# test.net
KiCad netlist of a schematic drawn in EAGLE
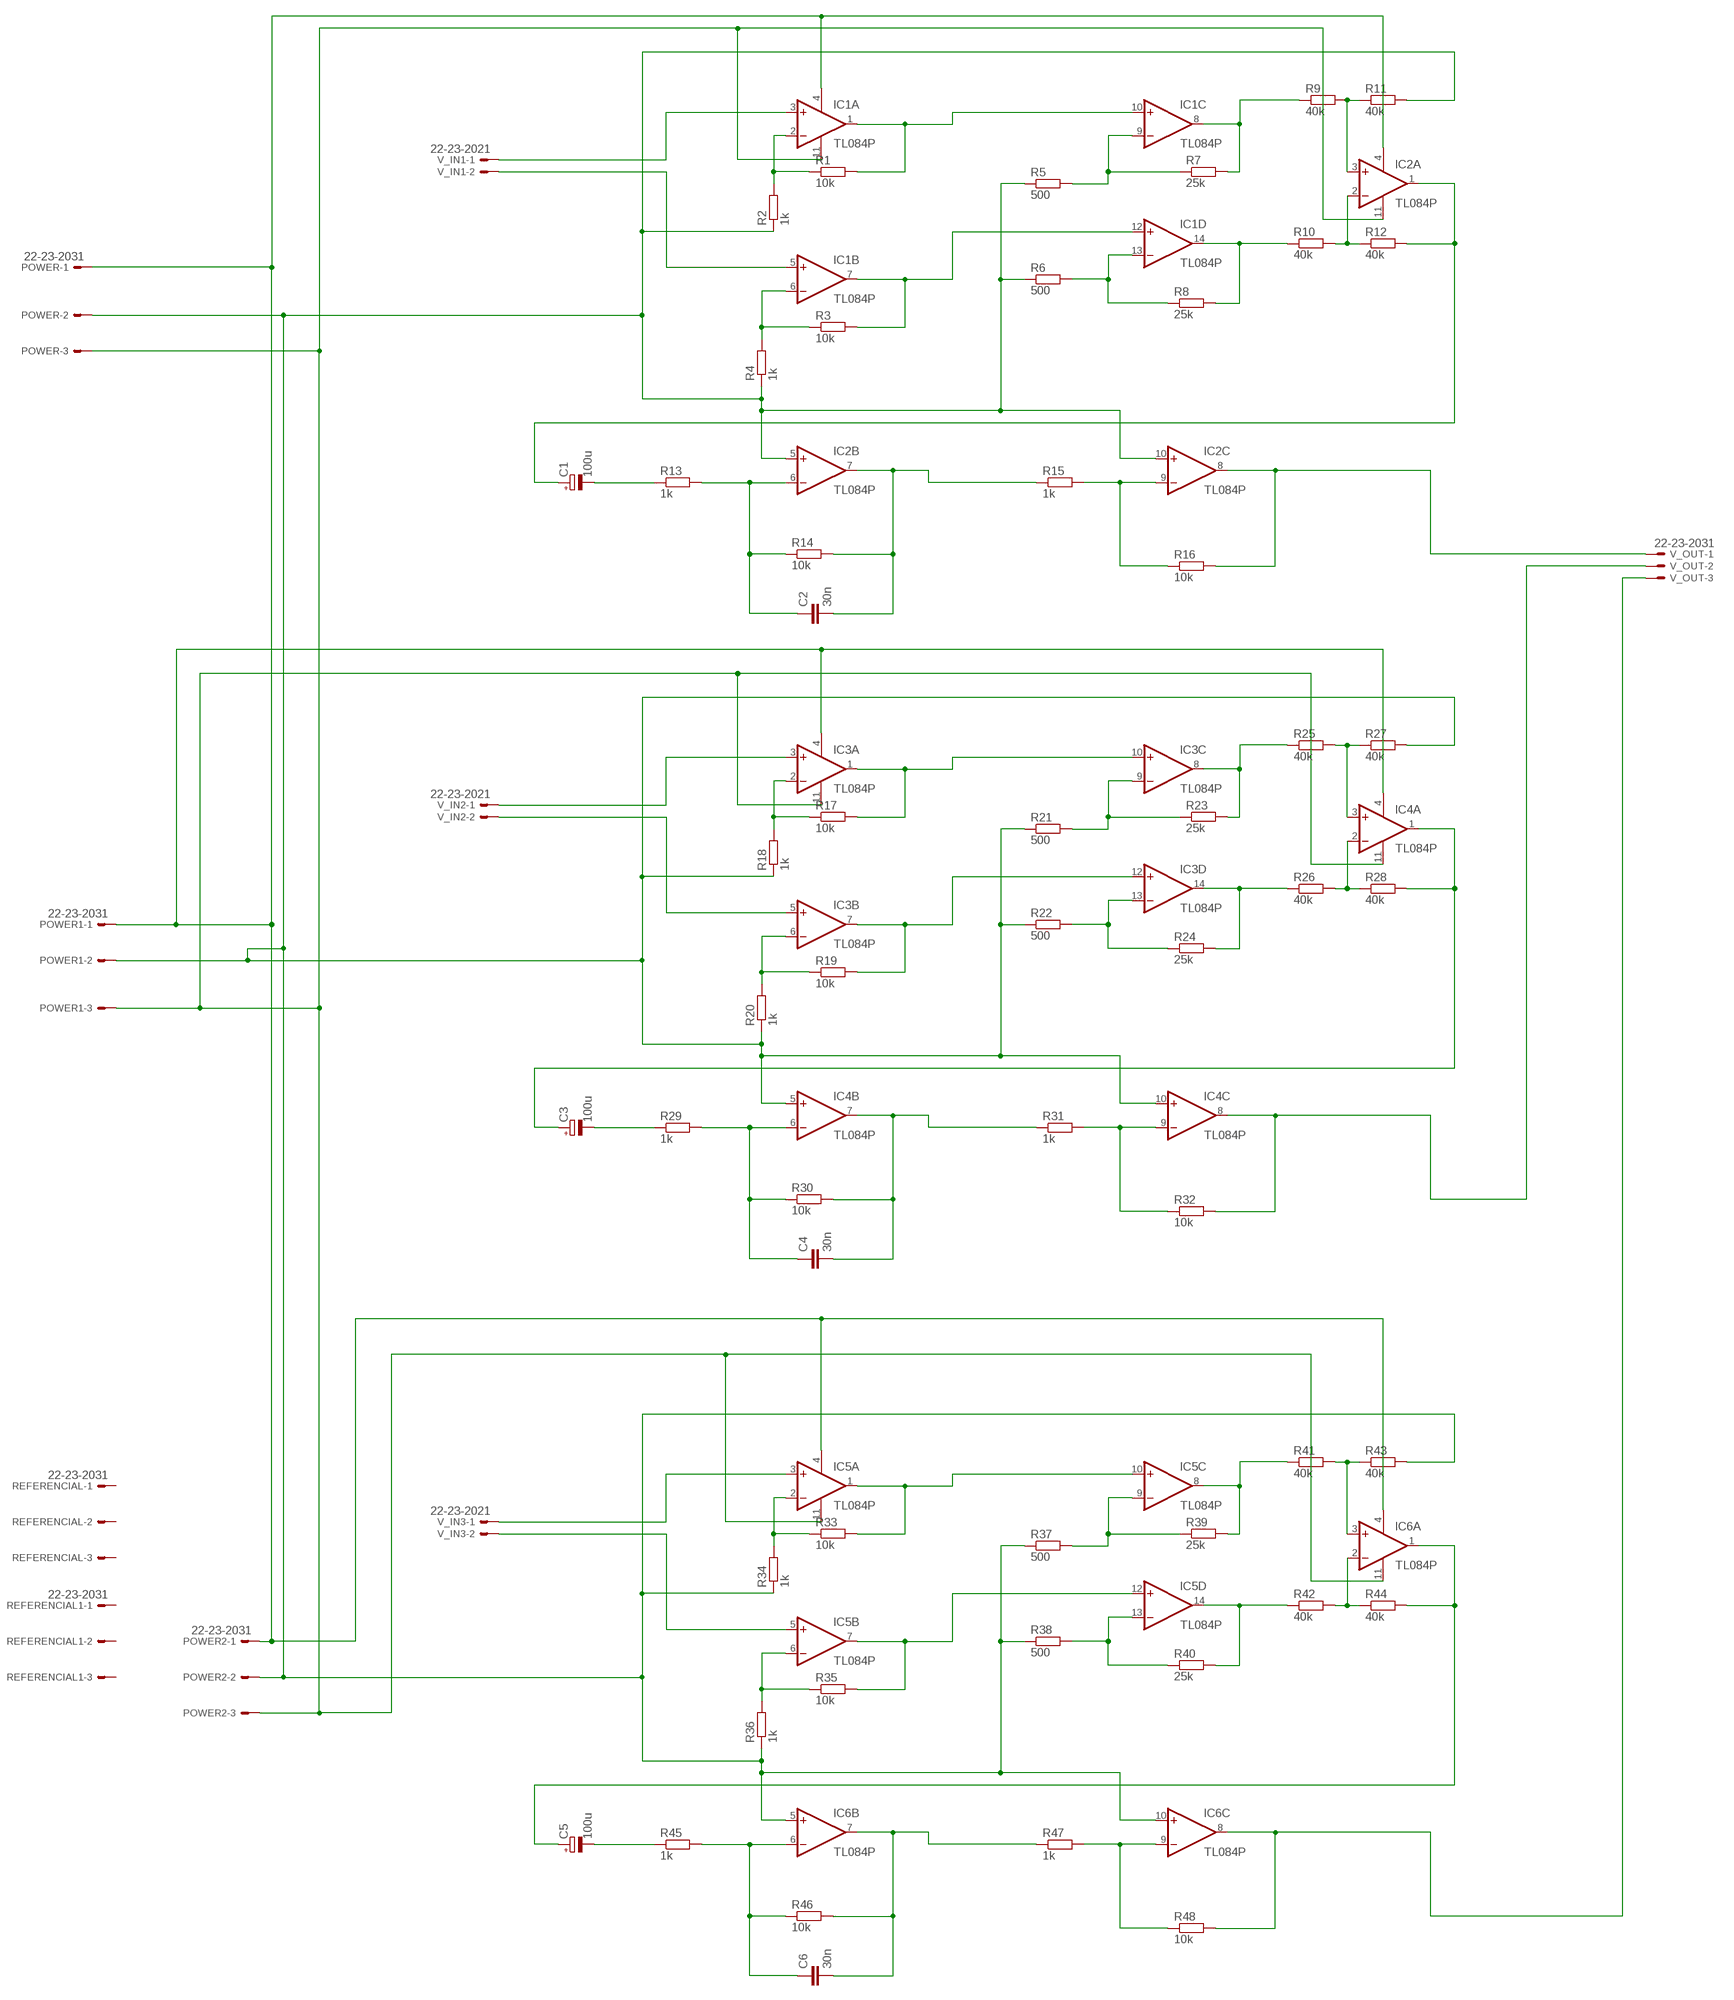
[diagram p0: schematic, sheet 1]

(export (version "E")
  (design (tool "Eeschema 10.0.6"))
  (components
    (comp (ref "C1")
      (value "100u")
      (footprint "eagle-import:E3,5-8")
      (libsource (lib "eagle-import") (part "CPOL-EUE3.5-8"))
    )
    (comp (ref "C2")
      (value "30n")
      (footprint "eagle-import:C050-024X044")
      (libsource (lib "eagle-import") (part "C-EU050-024X044"))
    )
    (comp (ref "C3")
      (value "100u")
      (footprint "eagle-import:E3,5-8")
      (libsource (lib "eagle-import") (part "CPOL-EUE3.5-8"))
    )
    (comp (ref "C4")
      (value "30n")
      (footprint "eagle-import:C050-024X044")
      (libsource (lib "eagle-import") (part "C-EU050-024X044"))
    )
    (comp (ref "C5")
      (value "100u")
      (footprint "eagle-import:E3,5-8")
      (libsource (lib "eagle-import") (part "CPOL-EUE3.5-8"))
    )
    (comp (ref "C6")
      (value "30n")
      (footprint "eagle-import:C050-024X044")
      (libsource (lib "eagle-import") (part "C-EU050-024X044"))
    )
    (comp (ref "IC1")
      (value "TL084P")
      (footprint "eagle-import:DIL14")
      (libsource (lib "eagle-import") (part "TL084P"))
    )
    (comp (ref "IC2")
      (value "TL084P")
      (footprint "eagle-import:DIL14")
      (libsource (lib "eagle-import") (part "TL084P"))
    )
    (comp (ref "IC3")
      (value "TL084P")
      (footprint "eagle-import:DIL14")
      (libsource (lib "eagle-import") (part "TL084P"))
    )
    (comp (ref "IC4")
      (value "TL084P")
      (footprint "eagle-import:DIL14")
      (libsource (lib "eagle-import") (part "TL084P"))
    )
    (comp (ref "IC5")
      (value "TL084P")
      (footprint "eagle-import:DIL14")
      (libsource (lib "eagle-import") (part "TL084P"))
    )
    (comp (ref "IC6")
      (value "TL084P")
      (footprint "eagle-import:DIL14")
      (libsource (lib "eagle-import") (part "TL084P"))
    )
    (comp (ref "POWER")
      (value "22-23-2031")
      (footprint "eagle-import:22-23-2031")
      (fields (field (name "MF") "MOLEX"))
      (libsource (lib "eagle-import") (part "22-23-2031"))
    )
    (comp (ref "POWER1")
      (value "22-23-2031")
      (footprint "eagle-import:22-23-2031")
      (fields (field (name "MF") "MOLEX"))
      (libsource (lib "eagle-import") (part "22-23-2031"))
    )
    (comp (ref "POWER2")
      (value "22-23-2031")
      (footprint "eagle-import:22-23-2031")
      (fields (field (name "MF") "MOLEX"))
      (libsource (lib "eagle-import") (part "22-23-2031"))
    )
    (comp (ref "R1")
      (value "10k")
      (footprint "eagle-import:0207_10")
      (libsource (lib "eagle-import") (part "R-EU_0207/10"))
    )
    (comp (ref "R2")
      (value "1k")
      (footprint "eagle-import:0207_10")
      (libsource (lib "eagle-import") (part "R-EU_0207/10"))
    )
    (comp (ref "R3")
      (value "10k")
      (footprint "eagle-import:0207_10")
      (libsource (lib "eagle-import") (part "R-EU_0207/10"))
    )
    (comp (ref "R4")
      (value "1k")
      (footprint "eagle-import:0207_10")
      (libsource (lib "eagle-import") (part "R-EU_0207/10"))
    )
    (comp (ref "R5")
      (value "500")
      (footprint "eagle-import:0207_10")
      (libsource (lib "eagle-import") (part "R-EU_0207/10"))
    )
    (comp (ref "R6")
      (value "500")
      (footprint "eagle-import:0207_10")
      (libsource (lib "eagle-import") (part "R-EU_0207/10"))
    )
    (comp (ref "R7")
      (value "25k")
      (footprint "eagle-import:0207_10")
      (libsource (lib "eagle-import") (part "R-EU_0207/10"))
    )
    (comp (ref "R8")
      (value "25k")
      (footprint "eagle-import:0207_10")
      (libsource (lib "eagle-import") (part "R-EU_0207/10"))
    )
    (comp (ref "R9")
      (value "40k")
      (footprint "eagle-import:0207_10")
      (libsource (lib "eagle-import") (part "R-EU_0207/10"))
    )
    (comp (ref "R10")
      (value "40k")
      (footprint "eagle-import:0207_10")
      (libsource (lib "eagle-import") (part "R-EU_0207/10"))
    )
    (comp (ref "R11")
      (value "40k")
      (footprint "eagle-import:0207_10")
      (libsource (lib "eagle-import") (part "R-EU_0207/10"))
    )
    (comp (ref "R12")
      (value "40k")
      (footprint "eagle-import:0207_10")
      (libsource (lib "eagle-import") (part "R-EU_0207/10"))
    )
    (comp (ref "R13")
      (value "1k")
      (footprint "eagle-import:0207_10")
      (libsource (lib "eagle-import") (part "R-EU_0207/10"))
    )
    (comp (ref "R14")
      (value "10k")
      (footprint "eagle-import:0207_10")
      (libsource (lib "eagle-import") (part "R-EU_0207/10"))
    )
    (comp (ref "R15")
      (value "1k")
      (footprint "eagle-import:0207_10")
      (libsource (lib "eagle-import") (part "R-EU_0207/10"))
    )
    (comp (ref "R16")
      (value "10k")
      (footprint "eagle-import:0207_10")
      (libsource (lib "eagle-import") (part "R-EU_0207/10"))
    )
    (comp (ref "R17")
      (value "10k")
      (footprint "eagle-import:0207_10")
      (libsource (lib "eagle-import") (part "R-EU_0207/10"))
    )
    (comp (ref "R18")
      (value "1k")
      (footprint "eagle-import:0207_10")
      (libsource (lib "eagle-import") (part "R-EU_0207/10"))
    )
    (comp (ref "R19")
      (value "10k")
      (footprint "eagle-import:0207_10")
      (libsource (lib "eagle-import") (part "R-EU_0207/10"))
    )
    (comp (ref "R20")
      (value "1k")
      (footprint "eagle-import:0207_10")
      (libsource (lib "eagle-import") (part "R-EU_0207/10"))
    )
    (comp (ref "R21")
      (value "500")
      (footprint "eagle-import:0207_10")
      (libsource (lib "eagle-import") (part "R-EU_0207/10"))
    )
    (comp (ref "R22")
      (value "500")
      (footprint "eagle-import:0207_10")
      (libsource (lib "eagle-import") (part "R-EU_0207/10"))
    )
    (comp (ref "R23")
      (value "25k")
      (footprint "eagle-import:0207_10")
      (libsource (lib "eagle-import") (part "R-EU_0207/10"))
    )
    (comp (ref "R24")
      (value "25k")
      (footprint "eagle-import:0207_10")
      (libsource (lib "eagle-import") (part "R-EU_0207/10"))
    )
    (comp (ref "R25")
      (value "40k")
      (footprint "eagle-import:0207_10")
      (libsource (lib "eagle-import") (part "R-EU_0207/10"))
    )
    (comp (ref "R26")
      (value "40k")
      (footprint "eagle-import:0207_10")
      (libsource (lib "eagle-import") (part "R-EU_0207/10"))
    )
    (comp (ref "R27")
      (value "40k")
      (footprint "eagle-import:0207_10")
      (libsource (lib "eagle-import") (part "R-EU_0207/10"))
    )
    (comp (ref "R28")
      (value "40k")
      (footprint "eagle-import:0207_10")
      (libsource (lib "eagle-import") (part "R-EU_0207/10"))
    )
    (comp (ref "R29")
      (value "1k")
      (footprint "eagle-import:0207_10")
      (libsource (lib "eagle-import") (part "R-EU_0207/10"))
    )
    (comp (ref "R30")
      (value "10k")
      (footprint "eagle-import:0207_10")
      (libsource (lib "eagle-import") (part "R-EU_0207/10"))
    )
    (comp (ref "R31")
      (value "1k")
      (footprint "eagle-import:0207_10")
      (libsource (lib "eagle-import") (part "R-EU_0207/10"))
    )
    (comp (ref "R32")
      (value "10k")
      (footprint "eagle-import:0207_10")
      (libsource (lib "eagle-import") (part "R-EU_0207/10"))
    )
    (comp (ref "R33")
      (value "10k")
      (footprint "eagle-import:0207_10")
      (libsource (lib "eagle-import") (part "R-EU_0207/10"))
    )
    (comp (ref "R34")
      (value "1k")
      (footprint "eagle-import:0207_10")
      (libsource (lib "eagle-import") (part "R-EU_0207/10"))
    )
    (comp (ref "R35")
      (value "10k")
      (footprint "eagle-import:0207_10")
      (libsource (lib "eagle-import") (part "R-EU_0207/10"))
    )
    (comp (ref "R36")
      (value "1k")
      (footprint "eagle-import:0207_10")
      (libsource (lib "eagle-import") (part "R-EU_0207/10"))
    )
    (comp (ref "R37")
      (value "500")
      (footprint "eagle-import:0207_10")
      (libsource (lib "eagle-import") (part "R-EU_0207/10"))
    )
    (comp (ref "R38")
      (value "500")
      (footprint "eagle-import:0207_10")
      (libsource (lib "eagle-import") (part "R-EU_0207/10"))
    )
    (comp (ref "R39")
      (value "25k")
      (footprint "eagle-import:0207_10")
      (libsource (lib "eagle-import") (part "R-EU_0207/10"))
    )
    (comp (ref "R40")
      (value "25k")
      (footprint "eagle-import:0207_10")
      (libsource (lib "eagle-import") (part "R-EU_0207/10"))
    )
    (comp (ref "R41")
      (value "40k")
      (footprint "eagle-import:0207_10")
      (libsource (lib "eagle-import") (part "R-EU_0207/10"))
    )
    (comp (ref "R42")
      (value "40k")
      (footprint "eagle-import:0207_10")
      (libsource (lib "eagle-import") (part "R-EU_0207/10"))
    )
    (comp (ref "R43")
      (value "40k")
      (footprint "eagle-import:0207_10")
      (libsource (lib "eagle-import") (part "R-EU_0207/10"))
    )
    (comp (ref "R44")
      (value "40k")
      (footprint "eagle-import:0207_10")
      (libsource (lib "eagle-import") (part "R-EU_0207/10"))
    )
    (comp (ref "R45")
      (value "1k")
      (footprint "eagle-import:0207_10")
      (libsource (lib "eagle-import") (part "R-EU_0207/10"))
    )
    (comp (ref "R46")
      (value "10k")
      (footprint "eagle-import:0207_10")
      (libsource (lib "eagle-import") (part "R-EU_0207/10"))
    )
    (comp (ref "R47")
      (value "1k")
      (footprint "eagle-import:0207_10")
      (libsource (lib "eagle-import") (part "R-EU_0207/10"))
    )
    (comp (ref "R48")
      (value "10k")
      (footprint "eagle-import:0207_10")
      (libsource (lib "eagle-import") (part "R-EU_0207/10"))
    )
    (comp (ref "REFERENCIAL")
      (value "22-23-2031")
      (footprint "eagle-import:22-23-2031")
      (fields (field (name "MF") "MOLEX"))
      (libsource (lib "eagle-import") (part "22-23-2031"))
    )
    (comp (ref "REFERENCIAL1")
      (value "22-23-2031")
      (footprint "eagle-import:22-23-2031")
      (fields (field (name "MF") "MOLEX"))
      (libsource (lib "eagle-import") (part "22-23-2031"))
    )
    (comp (ref "V_IN1")
      (value "22-23-2021")
      (footprint "eagle-import:22-23-2021")
      (fields (field (name "MF") "MOLEX"))
      (libsource (lib "eagle-import") (part "22-23-2021"))
    )
    (comp (ref "V_IN2")
      (value "22-23-2021")
      (footprint "eagle-import:22-23-2021")
      (fields (field (name "MF") "MOLEX"))
      (libsource (lib "eagle-import") (part "22-23-2021"))
    )
    (comp (ref "V_IN3")
      (value "22-23-2021")
      (footprint "eagle-import:22-23-2021")
      (fields (field (name "MF") "MOLEX"))
      (libsource (lib "eagle-import") (part "22-23-2021"))
    )
    (comp (ref "V_OUT")
      (value "22-23-2031")
      (footprint "eagle-import:22-23-2031")
      (fields (field (name "MF") "MOLEX"))
      (libsource (lib "eagle-import") (part "22-23-2031"))
    )
  )
  (nets
    (net (code "1") (name "Net-(C1-Pad-)") (class "Default")
      (node (ref "C1") (pin "-") (pinfunction "-_-") (pintype "passive"))
      (node (ref "R13") (pin "1") (pinfunction "1_1") (pintype "passive"))
    )
    (net (code "2") (name "Net-(C3-Pad-)") (class "Default")
      (node (ref "C3") (pin "-") (pinfunction "-_-") (pintype "passive"))
      (node (ref "R29") (pin "1") (pinfunction "1_1") (pintype "passive"))
    )
    (net (code "3") (name "Net-(C5-Pad-)") (class "Default")
      (node (ref "C5") (pin "-") (pinfunction "-_-") (pintype "passive"))
      (node (ref "R45") (pin "1") (pinfunction "1_1") (pintype "passive"))
    )
    (net (code "4") (name "Net-(IC1A-+IN)") (class "Default")
      (node (ref "IC1") (pin "3") (pinfunction "+IN_3") (pintype "input"))
      (node (ref "V_IN1") (pin "1") (pinfunction "S_1") (pintype "passive"))
    )
    (net (code "5") (name "Net-(IC1A--IN)") (class "Default")
      (node (ref "IC1") (pin "2") (pinfunction "-IN_2") (pintype "input"))
      (node (ref "R1") (pin "1") (pinfunction "1_1") (pintype "passive"))
      (node (ref "R2") (pin "2") (pinfunction "2_2") (pintype "passive"))
    )
    (net (code "6") (name "Net-(IC1A-OUT)") (class "Default")
      (node (ref "IC1") (pin "1") (pinfunction "OUT_1") (pintype "output"))
      (node (ref "IC1") (pin "10") (pinfunction "+IN_10") (pintype "input"))
      (node (ref "R1") (pin "2") (pinfunction "2_2") (pintype "passive"))
    )
    (net (code "7") (name "Net-(IC1B-+IN)") (class "Default")
      (node (ref "IC1") (pin "5") (pinfunction "+IN_5") (pintype "input"))
      (node (ref "V_IN1") (pin "2") (pinfunction "S_2") (pintype "passive"))
    )
    (net (code "8") (name "Net-(IC1B--IN)") (class "Default")
      (node (ref "IC1") (pin "6") (pinfunction "-IN_6") (pintype "input"))
      (node (ref "R3") (pin "1") (pinfunction "1_1") (pintype "passive"))
      (node (ref "R4") (pin "2") (pinfunction "2_2") (pintype "passive"))
    )
    (net (code "9") (name "Net-(IC1B-OUT)") (class "Default")
      (node (ref "IC1") (pin "12") (pinfunction "+IN_12") (pintype "input"))
      (node (ref "IC1") (pin "7") (pinfunction "OUT_7") (pintype "output"))
      (node (ref "R3") (pin "2") (pinfunction "2_2") (pintype "passive"))
    )
    (net (code "10") (name "Net-(IC1C--IN)") (class "Default")
      (node (ref "IC1") (pin "9") (pinfunction "-IN_9") (pintype "input"))
      (node (ref "R5") (pin "2") (pinfunction "2_2") (pintype "passive"))
      (node (ref "R7") (pin "1") (pinfunction "1_1") (pintype "passive"))
    )
    (net (code "11") (name "Net-(IC1C-OUT)") (class "Default")
      (node (ref "IC1") (pin "8") (pinfunction "OUT_8") (pintype "output"))
      (node (ref "R7") (pin "2") (pinfunction "2_2") (pintype "passive"))
      (node (ref "R9") (pin "1") (pinfunction "1_1") (pintype "passive"))
    )
    (net (code "12") (name "Net-(IC1D--IN)") (class "Default")
      (node (ref "IC1") (pin "13") (pinfunction "-IN_13") (pintype "input"))
      (node (ref "R6") (pin "2") (pinfunction "2_2") (pintype "passive"))
      (node (ref "R8") (pin "1") (pinfunction "1_1") (pintype "passive"))
    )
    (net (code "13") (name "Net-(IC1D-OUT)") (class "Default")
      (node (ref "IC1") (pin "14") (pinfunction "OUT_14") (pintype "output"))
      (node (ref "R10") (pin "1") (pinfunction "1_1") (pintype "passive"))
      (node (ref "R8") (pin "2") (pinfunction "2_2") (pintype "passive"))
    )
    (net (code "14") (name "Net-(IC1E-V+)") (class "Default")
      (node (ref "IC1") (pin "4") (pinfunction "V+_4") (pintype "power_in"))
      (node (ref "IC2") (pin "4") (pinfunction "V+_4") (pintype "power_in"))
      (node (ref "IC3") (pin "4") (pinfunction "V+_4") (pintype "power_in"))
      (node (ref "IC4") (pin "4") (pinfunction "V+_4") (pintype "power_in"))
      (node (ref "IC5") (pin "4") (pinfunction "V+_4") (pintype "power_in"))
      (node (ref "IC6") (pin "4") (pinfunction "V+_4") (pintype "power_in"))
      (node (ref "POWER") (pin "1") (pinfunction "S_1") (pintype "passive"))
      (node (ref "POWER1") (pin "1") (pinfunction "S_1") (pintype "passive"))
      (node (ref "POWER2") (pin "1") (pinfunction "S_1") (pintype "passive"))
    )
    (net (code "15") (name "Net-(IC1E-V-)") (class "Default")
      (node (ref "IC1") (pin "11") (pinfunction "V-_11") (pintype "power_in"))
      (node (ref "IC2") (pin "11") (pinfunction "V-_11") (pintype "power_in"))
      (node (ref "IC3") (pin "11") (pinfunction "V-_11") (pintype "power_in"))
      (node (ref "IC4") (pin "11") (pinfunction "V-_11") (pintype "power_in"))
      (node (ref "IC5") (pin "11") (pinfunction "V-_11") (pintype "power_in"))
      (node (ref "IC6") (pin "11") (pinfunction "V-_11") (pintype "power_in"))
      (node (ref "POWER") (pin "3") (pinfunction "S_3") (pintype "passive"))
      (node (ref "POWER1") (pin "3") (pinfunction "S_3") (pintype "passive"))
      (node (ref "POWER2") (pin "3") (pinfunction "S_3") (pintype "passive"))
    )
    (net (code "16") (name "Net-(IC2A-+IN)") (class "Default")
      (node (ref "IC2") (pin "3") (pinfunction "+IN_3") (pintype "input"))
      (node (ref "R11") (pin "1") (pinfunction "1_1") (pintype "passive"))
      (node (ref "R9") (pin "2") (pinfunction "2_2") (pintype "passive"))
    )
    (net (code "17") (name "Net-(IC2A--IN)") (class "Default")
      (node (ref "IC2") (pin "2") (pinfunction "-IN_2") (pintype "input"))
      (node (ref "R10") (pin "2") (pinfunction "2_2") (pintype "passive"))
      (node (ref "R12") (pin "1") (pinfunction "1_1") (pintype "passive"))
    )
    (net (code "18") (name "Net-(IC2A-OUT)") (class "Default")
      (node (ref "C1") (pin "+") (pinfunction "+_+") (pintype "passive"))
      (node (ref "IC2") (pin "1") (pinfunction "OUT_1") (pintype "output"))
      (node (ref "R12") (pin "2") (pinfunction "2_2") (pintype "passive"))
    )
    (net (code "19") (name "Net-(IC2B-+IN)") (class "Default")
      (node (ref "IC2") (pin "10") (pinfunction "+IN_10") (pintype "input"))
      (node (ref "IC2") (pin "5") (pinfunction "+IN_5") (pintype "input"))
      (node (ref "IC4") (pin "10") (pinfunction "+IN_10") (pintype "input"))
      (node (ref "IC4") (pin "5") (pinfunction "+IN_5") (pintype "input"))
      (node (ref "IC6") (pin "10") (pinfunction "+IN_10") (pintype "input"))
      (node (ref "IC6") (pin "5") (pinfunction "+IN_5") (pintype "input"))
      (node (ref "POWER") (pin "2") (pinfunction "S_2") (pintype "passive"))
      (node (ref "POWER1") (pin "2") (pinfunction "S_2") (pintype "passive"))
      (node (ref "POWER2") (pin "2") (pinfunction "S_2") (pintype "passive"))
      (node (ref "R11") (pin "2") (pinfunction "2_2") (pintype "passive"))
      (node (ref "R18") (pin "1") (pinfunction "1_1") (pintype "passive"))
      (node (ref "R2") (pin "1") (pinfunction "1_1") (pintype "passive"))
      (node (ref "R20") (pin "1") (pinfunction "1_1") (pintype "passive"))
      (node (ref "R21") (pin "1") (pinfunction "1_1") (pintype "passive"))
      (node (ref "R22") (pin "1") (pinfunction "1_1") (pintype "passive"))
      (node (ref "R27") (pin "2") (pinfunction "2_2") (pintype "passive"))
      (node (ref "R34") (pin "1") (pinfunction "1_1") (pintype "passive"))
      (node (ref "R36") (pin "1") (pinfunction "1_1") (pintype "passive"))
      (node (ref "R37") (pin "1") (pinfunction "1_1") (pintype "passive"))
      (node (ref "R38") (pin "1") (pinfunction "1_1") (pintype "passive"))
      (node (ref "R4") (pin "1") (pinfunction "1_1") (pintype "passive"))
      (node (ref "R43") (pin "2") (pinfunction "2_2") (pintype "passive"))
      (node (ref "R5") (pin "1") (pinfunction "1_1") (pintype "passive"))
      (node (ref "R6") (pin "1") (pinfunction "1_1") (pintype "passive"))
    )
    (net (code "20") (name "Net-(IC2B--IN)") (class "Default")
      (node (ref "C2") (pin "1") (pinfunction "1_1") (pintype "passive"))
      (node (ref "IC2") (pin "6") (pinfunction "-IN_6") (pintype "input"))
      (node (ref "R13") (pin "2") (pinfunction "2_2") (pintype "passive"))
      (node (ref "R14") (pin "1") (pinfunction "1_1") (pintype "passive"))
    )
    (net (code "21") (name "Net-(IC2B-OUT)") (class "Default")
      (node (ref "C2") (pin "2") (pinfunction "2_2") (pintype "passive"))
      (node (ref "IC2") (pin "7") (pinfunction "OUT_7") (pintype "output"))
      (node (ref "R14") (pin "2") (pinfunction "2_2") (pintype "passive"))
      (node (ref "R15") (pin "1") (pinfunction "1_1") (pintype "passive"))
    )
    (net (code "22") (name "Net-(IC2C--IN)") (class "Default")
      (node (ref "IC2") (pin "9") (pinfunction "-IN_9") (pintype "input"))
      (node (ref "R15") (pin "2") (pinfunction "2_2") (pintype "passive"))
      (node (ref "R16") (pin "1") (pinfunction "1_1") (pintype "passive"))
    )
    (net (code "23") (name "Net-(IC2C-OUT)") (class "Default")
      (node (ref "IC2") (pin "8") (pinfunction "OUT_8") (pintype "output"))
      (node (ref "R16") (pin "2") (pinfunction "2_2") (pintype "passive"))
      (node (ref "V_OUT") (pin "1") (pinfunction "S_1") (pintype "passive"))
    )
    (net (code "24") (name "Net-(IC3A-+IN)") (class "Default")
      (node (ref "IC3") (pin "3") (pinfunction "+IN_3") (pintype "input"))
      (node (ref "V_IN2") (pin "1") (pinfunction "S_1") (pintype "passive"))
    )
    (net (code "25") (name "Net-(IC3A--IN)") (class "Default")
      (node (ref "IC3") (pin "2") (pinfunction "-IN_2") (pintype "input"))
      (node (ref "R17") (pin "1") (pinfunction "1_1") (pintype "passive"))
      (node (ref "R18") (pin "2") (pinfunction "2_2") (pintype "passive"))
    )
    (net (code "26") (name "Net-(IC3A-OUT)") (class "Default")
      (node (ref "IC3") (pin "1") (pinfunction "OUT_1") (pintype "output"))
      (node (ref "IC3") (pin "10") (pinfunction "+IN_10") (pintype "input"))
      (node (ref "R17") (pin "2") (pinfunction "2_2") (pintype "passive"))
    )
    (net (code "27") (name "Net-(IC3B-+IN)") (class "Default")
      (node (ref "IC3") (pin "5") (pinfunction "+IN_5") (pintype "input"))
      (node (ref "V_IN2") (pin "2") (pinfunction "S_2") (pintype "passive"))
    )
    (net (code "28") (name "Net-(IC3B--IN)") (class "Default")
      (node (ref "IC3") (pin "6") (pinfunction "-IN_6") (pintype "input"))
      (node (ref "R19") (pin "1") (pinfunction "1_1") (pintype "passive"))
      (node (ref "R20") (pin "2") (pinfunction "2_2") (pintype "passive"))
    )
    (net (code "29") (name "Net-(IC3B-OUT)") (class "Default")
      (node (ref "IC3") (pin "12") (pinfunction "+IN_12") (pintype "input"))
      (node (ref "IC3") (pin "7") (pinfunction "OUT_7") (pintype "output"))
      (node (ref "R19") (pin "2") (pinfunction "2_2") (pintype "passive"))
    )
    (net (code "30") (name "Net-(IC3C--IN)") (class "Default")
      (node (ref "IC3") (pin "9") (pinfunction "-IN_9") (pintype "input"))
      (node (ref "R21") (pin "2") (pinfunction "2_2") (pintype "passive"))
      (node (ref "R23") (pin "1") (pinfunction "1_1") (pintype "passive"))
    )
    (net (code "31") (name "Net-(IC3C-OUT)") (class "Default")
      (node (ref "IC3") (pin "8") (pinfunction "OUT_8") (pintype "output"))
      (node (ref "R23") (pin "2") (pinfunction "2_2") (pintype "passive"))
      (node (ref "R25") (pin "1") (pinfunction "1_1") (pintype "passive"))
    )
    (net (code "32") (name "Net-(IC3D--IN)") (class "Default")
      (node (ref "IC3") (pin "13") (pinfunction "-IN_13") (pintype "input"))
      (node (ref "R22") (pin "2") (pinfunction "2_2") (pintype "passive"))
      (node (ref "R24") (pin "1") (pinfunction "1_1") (pintype "passive"))
    )
    (net (code "33") (name "Net-(IC3D-OUT)") (class "Default")
      (node (ref "IC3") (pin "14") (pinfunction "OUT_14") (pintype "output"))
      (node (ref "R24") (pin "2") (pinfunction "2_2") (pintype "passive"))
      (node (ref "R26") (pin "1") (pinfunction "1_1") (pintype "passive"))
    )
    (net (code "34") (name "Net-(IC4A-+IN)") (class "Default")
      (node (ref "IC4") (pin "3") (pinfunction "+IN_3") (pintype "input"))
      (node (ref "R25") (pin "2") (pinfunction "2_2") (pintype "passive"))
      (node (ref "R27") (pin "1") (pinfunction "1_1") (pintype "passive"))
    )
    (net (code "35") (name "Net-(IC4A--IN)") (class "Default")
      (node (ref "IC4") (pin "2") (pinfunction "-IN_2") (pintype "input"))
      (node (ref "R26") (pin "2") (pinfunction "2_2") (pintype "passive"))
      (node (ref "R28") (pin "1") (pinfunction "1_1") (pintype "passive"))
    )
    (net (code "36") (name "Net-(IC4A-OUT)") (class "Default")
      (node (ref "C3") (pin "+") (pinfunction "+_+") (pintype "passive"))
      (node (ref "IC4") (pin "1") (pinfunction "OUT_1") (pintype "output"))
      (node (ref "R28") (pin "2") (pinfunction "2_2") (pintype "passive"))
    )
    (net (code "37") (name "Net-(IC4B--IN)") (class "Default")
      (node (ref "C4") (pin "1") (pinfunction "1_1") (pintype "passive"))
      (node (ref "IC4") (pin "6") (pinfunction "-IN_6") (pintype "input"))
      (node (ref "R29") (pin "2") (pinfunction "2_2") (pintype "passive"))
      (node (ref "R30") (pin "1") (pinfunction "1_1") (pintype "passive"))
    )
    (net (code "38") (name "Net-(IC4B-OUT)") (class "Default")
      (node (ref "C4") (pin "2") (pinfunction "2_2") (pintype "passive"))
      (node (ref "IC4") (pin "7") (pinfunction "OUT_7") (pintype "output"))
      (node (ref "R30") (pin "2") (pinfunction "2_2") (pintype "passive"))
      (node (ref "R31") (pin "1") (pinfunction "1_1") (pintype "passive"))
    )
    (net (code "39") (name "Net-(IC4C--IN)") (class "Default")
      (node (ref "IC4") (pin "9") (pinfunction "-IN_9") (pintype "input"))
      (node (ref "R31") (pin "2") (pinfunction "2_2") (pintype "passive"))
      (node (ref "R32") (pin "1") (pinfunction "1_1") (pintype "passive"))
    )
    (net (code "40") (name "Net-(IC4C-OUT)") (class "Default")
      (node (ref "IC4") (pin "8") (pinfunction "OUT_8") (pintype "output"))
      (node (ref "R32") (pin "2") (pinfunction "2_2") (pintype "passive"))
      (node (ref "V_OUT") (pin "2") (pinfunction "S_2") (pintype "passive"))
    )
    (net (code "41") (name "Net-(IC5A-+IN)") (class "Default")
      (node (ref "IC5") (pin "3") (pinfunction "+IN_3") (pintype "input"))
      (node (ref "V_IN3") (pin "1") (pinfunction "S_1") (pintype "passive"))
    )
    (net (code "42") (name "Net-(IC5A--IN)") (class "Default")
      (node (ref "IC5") (pin "2") (pinfunction "-IN_2") (pintype "input"))
      (node (ref "R33") (pin "1") (pinfunction "1_1") (pintype "passive"))
      (node (ref "R34") (pin "2") (pinfunction "2_2") (pintype "passive"))
    )
    (net (code "43") (name "Net-(IC5A-OUT)") (class "Default")
      (node (ref "IC5") (pin "1") (pinfunction "OUT_1") (pintype "output"))
      (node (ref "IC5") (pin "10") (pinfunction "+IN_10") (pintype "input"))
      (node (ref "R33") (pin "2") (pinfunction "2_2") (pintype "passive"))
    )
    (net (code "44") (name "Net-(IC5B-+IN)") (class "Default")
      (node (ref "IC5") (pin "5") (pinfunction "+IN_5") (pintype "input"))
      (node (ref "V_IN3") (pin "2") (pinfunction "S_2") (pintype "passive"))
    )
    (net (code "45") (name "Net-(IC5B--IN)") (class "Default")
      (node (ref "IC5") (pin "6") (pinfunction "-IN_6") (pintype "input"))
      (node (ref "R35") (pin "1") (pinfunction "1_1") (pintype "passive"))
      (node (ref "R36") (pin "2") (pinfunction "2_2") (pintype "passive"))
    )
    (net (code "46") (name "Net-(IC5B-OUT)") (class "Default")
      (node (ref "IC5") (pin "12") (pinfunction "+IN_12") (pintype "input"))
      (node (ref "IC5") (pin "7") (pinfunction "OUT_7") (pintype "output"))
      (node (ref "R35") (pin "2") (pinfunction "2_2") (pintype "passive"))
    )
    (net (code "47") (name "Net-(IC5C--IN)") (class "Default")
      (node (ref "IC5") (pin "9") (pinfunction "-IN_9") (pintype "input"))
      (node (ref "R37") (pin "2") (pinfunction "2_2") (pintype "passive"))
      (node (ref "R39") (pin "1") (pinfunction "1_1") (pintype "passive"))
    )
    (net (code "48") (name "Net-(IC5C-OUT)") (class "Default")
      (node (ref "IC5") (pin "8") (pinfunction "OUT_8") (pintype "output"))
      (node (ref "R39") (pin "2") (pinfunction "2_2") (pintype "passive"))
      (node (ref "R41") (pin "1") (pinfunction "1_1") (pintype "passive"))
    )
    (net (code "49") (name "Net-(IC5D--IN)") (class "Default")
      (node (ref "IC5") (pin "13") (pinfunction "-IN_13") (pintype "input"))
      (node (ref "R38") (pin "2") (pinfunction "2_2") (pintype "passive"))
      (node (ref "R40") (pin "1") (pinfunction "1_1") (pintype "passive"))
    )
    (net (code "50") (name "Net-(IC5D-OUT)") (class "Default")
      (node (ref "IC5") (pin "14") (pinfunction "OUT_14") (pintype "output"))
      (node (ref "R40") (pin "2") (pinfunction "2_2") (pintype "passive"))
      (node (ref "R42") (pin "1") (pinfunction "1_1") (pintype "passive"))
    )
    (net (code "51") (name "Net-(IC6A-+IN)") (class "Default")
      (node (ref "IC6") (pin "3") (pinfunction "+IN_3") (pintype "input"))
      (node (ref "R41") (pin "2") (pinfunction "2_2") (pintype "passive"))
      (node (ref "R43") (pin "1") (pinfunction "1_1") (pintype "passive"))
    )
    (net (code "52") (name "Net-(IC6A--IN)") (class "Default")
      (node (ref "IC6") (pin "2") (pinfunction "-IN_2") (pintype "input"))
      (node (ref "R42") (pin "2") (pinfunction "2_2") (pintype "passive"))
      (node (ref "R44") (pin "1") (pinfunction "1_1") (pintype "passive"))
    )
    (net (code "53") (name "Net-(IC6A-OUT)") (class "Default")
      (node (ref "C5") (pin "+") (pinfunction "+_+") (pintype "passive"))
      (node (ref "IC6") (pin "1") (pinfunction "OUT_1") (pintype "output"))
      (node (ref "R44") (pin "2") (pinfunction "2_2") (pintype "passive"))
    )
    (net (code "54") (name "Net-(IC6B--IN)") (class "Default")
      (node (ref "C6") (pin "1") (pinfunction "1_1") (pintype "passive"))
      (node (ref "IC6") (pin "6") (pinfunction "-IN_6") (pintype "input"))
      (node (ref "R45") (pin "2") (pinfunction "2_2") (pintype "passive"))
      (node (ref "R46") (pin "1") (pinfunction "1_1") (pintype "passive"))
    )
    (net (code "55") (name "Net-(IC6B-OUT)") (class "Default")
      (node (ref "C6") (pin "2") (pinfunction "2_2") (pintype "passive"))
      (node (ref "IC6") (pin "7") (pinfunction "OUT_7") (pintype "output"))
      (node (ref "R46") (pin "2") (pinfunction "2_2") (pintype "passive"))
      (node (ref "R47") (pin "1") (pinfunction "1_1") (pintype "passive"))
    )
    (net (code "56") (name "Net-(IC6C--IN)") (class "Default")
      (node (ref "IC6") (pin "9") (pinfunction "-IN_9") (pintype "input"))
      (node (ref "R47") (pin "2") (pinfunction "2_2") (pintype "passive"))
      (node (ref "R48") (pin "1") (pinfunction "1_1") (pintype "passive"))
    )
    (net (code "57") (name "Net-(IC6C-OUT)") (class "Default")
      (node (ref "IC6") (pin "8") (pinfunction "OUT_8") (pintype "output"))
      (node (ref "R48") (pin "2") (pinfunction "2_2") (pintype "passive"))
      (node (ref "V_OUT") (pin "3") (pinfunction "S_3") (pintype "passive"))
    )
    (net (code "58") (name "unconnected-(REFERENCIAL1A-S-Pad1)") (class "Default")
      (node (ref "REFERENCIAL1") (pin "1") (pinfunction "S_1") (pintype "passive"))
    )
    (net (code "59") (name "unconnected-(REFERENCIAL1B-S-Pad2)") (class "Default")
      (node (ref "REFERENCIAL1") (pin "2") (pinfunction "S_2") (pintype "passive"))
    )
    (net (code "60") (name "unconnected-(REFERENCIAL1C-S-Pad3)") (class "Default")
      (node (ref "REFERENCIAL1") (pin "3") (pinfunction "S_3") (pintype "passive"))
    )
    (net (code "61") (name "unconnected-(REFERENCIALA-S-Pad1)") (class "Default")
      (node (ref "REFERENCIAL") (pin "1") (pinfunction "S_1") (pintype "passive"))
    )
    (net (code "62") (name "unconnected-(REFERENCIALB-S-Pad2)") (class "Default")
      (node (ref "REFERENCIAL") (pin "2") (pinfunction "S_2") (pintype "passive"))
    )
    (net (code "63") (name "unconnected-(REFERENCIALC-S-Pad3)") (class "Default")
      (node (ref "REFERENCIAL") (pin "3") (pinfunction "S_3") (pintype "passive"))
    )
  )
)
